# Sheet2.net
KiCad netlist of a schematic drawn in Altium Designer
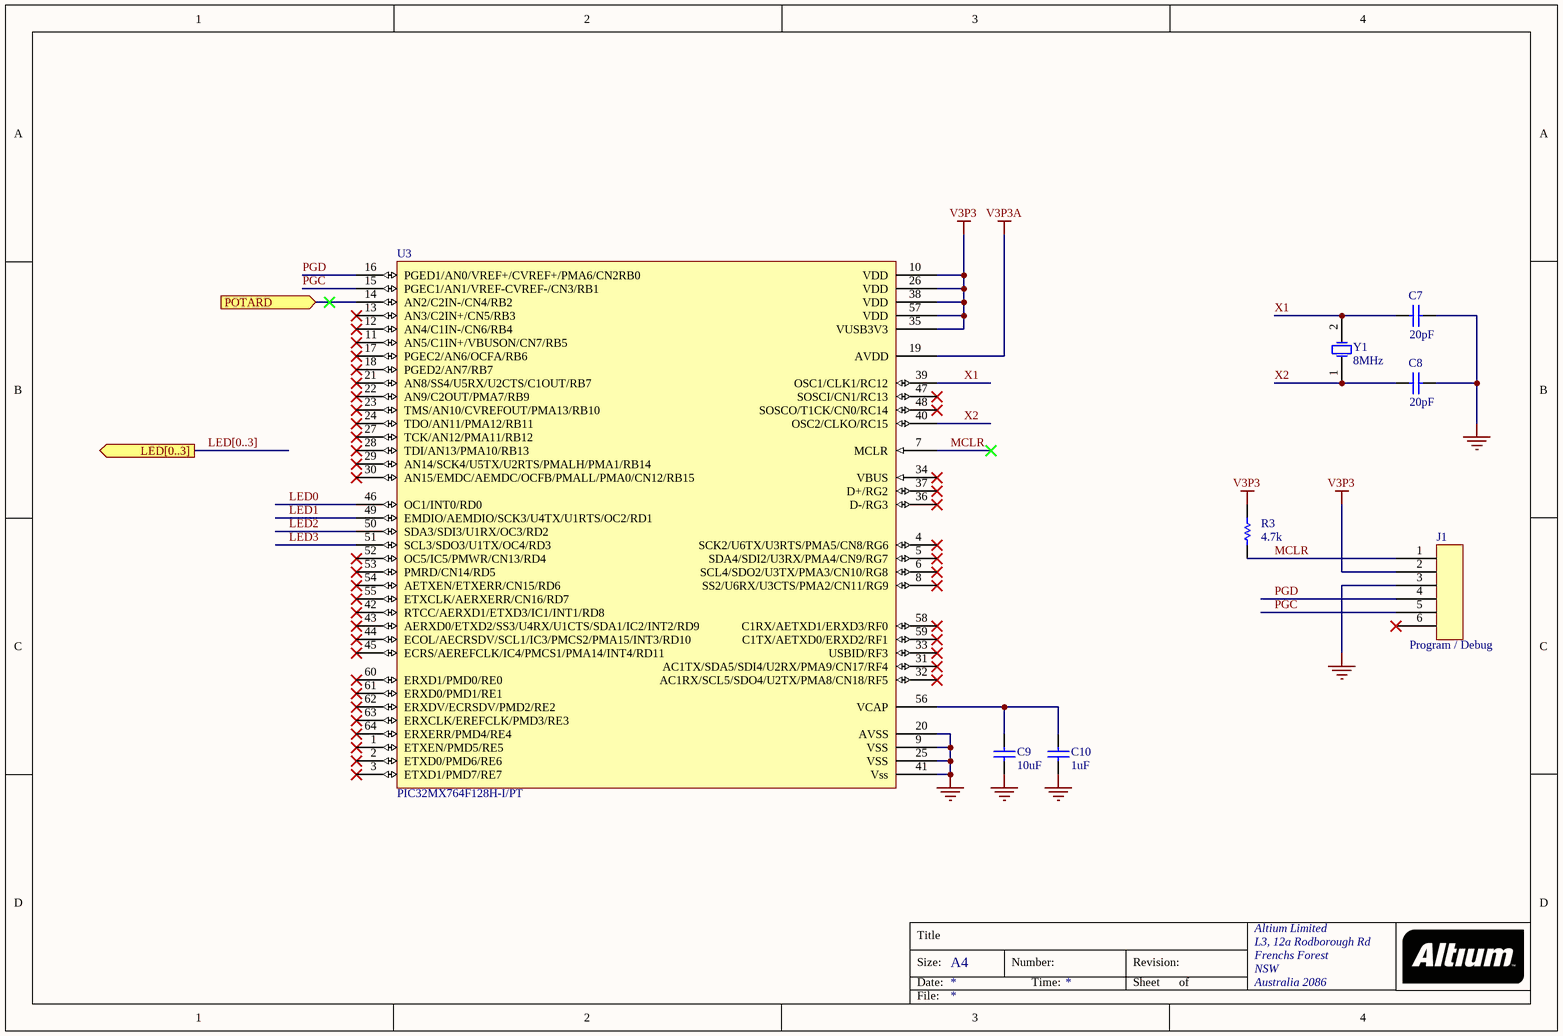
[diagram p0: Sheet2.SchDoc]

(export (version "E")
  (design (tool "Eeschema 10.0.6"))
  (components
    (comp (ref "C7")
      (value "20pF")
      (footprint "RAD-0.3")
      (description "Capacitor")
      (fields (field (name "Comment") "Cap") (field (name "PUBLISHER") "Altium Limited"))
      (libsource (lib "Miscellaneous Devices") (part "Cap"))
    )
    (comp (ref "C8")
      (value "20pF")
      (footprint "RAD-0.3")
      (description "Capacitor")
      (fields (field (name "Comment") "Cap") (field (name "PUBLISHER") "Altium Limited"))
      (libsource (lib "Miscellaneous Devices") (part "Cap"))
    )
    (comp (ref "C9")
      (value "10uF")
      (footprint "RAD-0.3")
      (description "Capacitor")
      (fields (field (name "Comment") "Cap") (field (name "PUBLISHER") "Altium Limited"))
      (libsource (lib "Miscellaneous Devices") (part "Cap"))
    )
    (comp (ref "C10")
      (value "1uF")
      (footprint "RAD-0.3")
      (description "Capacitor")
      (fields (field (name "Comment") "Cap") (field (name "PUBLISHER") "Altium Limited"))
      (libsource (lib "Miscellaneous Devices") (part "Cap"))
    )
    (comp (ref "J1") (value "Program / Debug") (libsource (lib "SchDebug") (part "Component_1")))
    (comp (ref "R3")
      (value "4.7k")
      (footprint "AXIAL-0.3")
      (description "Resistor")
      (fields (field (name "Comment") "Res1") (field (name "PUBLISHER") "Altium Limited"))
      (libsource (lib "Miscellaneous Devices") (part "Res1"))
    )
    (comp (ref "U3") (value "PIC32MX764F128H-I/PT") (libsource (lib "SchDebug") (part "PIC 32")))
    (comp (ref "Y1")
      (value "8MHz")
      (footprint "Fox Quartz")
      (description "Crystal Oscillator")
      (fields (field (name "PUBLISHER") "Altium Limited"))
      (libsource (lib "Miscellaneous Devices") (part "XTAL"))
    )
  )
  (nets
    (net (code "1") (name "/LED0") (class "Default")
      (node (ref "U3") (pin "46") (pinfunction "OC1/INT0/RD0_46") (pintype "bidirectional"))
    )
    (net (code "2") (name "/LED1") (class "Default")
      (node (ref "U3") (pin "49") (pinfunction "EMDIO/AEMDIO/SCK3/U4TX/U1RTS/OC2/RD1_49") (pintype "bidirectional"))
    )
    (net (code "3") (name "/LED2") (class "Default")
      (node (ref "U3") (pin "50") (pinfunction "SDA3/SDI3/U1RX/OC3/RD2_50") (pintype "bidirectional"))
    )
    (net (code "4") (name "/LED3") (class "Default")
      (node (ref "U3") (pin "51") (pinfunction "SCL3/SDO3/U1TX/OC4/RD3_51") (pintype "bidirectional"))
    )
    (net (code "6") (name "/MCLR") (class "Default")
      (node (ref "J1") (pin "1") (pinfunction "1_1") (pintype "passive"))
      (node (ref "R3") (pin "1") (pinfunction "1_1") (pintype "passive"))
      (node (ref "U3") (pin "7") (pinfunction "MCLR_7") (pintype "input"))
    )
    (net (code "7") (name "/PGC") (class "Default")
      (node (ref "J1") (pin "5") (pinfunction "5_5") (pintype "passive"))
      (node (ref "U3") (pin "15") (pinfunction "PGEC1/AN1/VREF-CVREF-/CN3/RB1_15") (pintype "bidirectional"))
    )
    (net (code "8") (name "/PGD") (class "Default")
      (node (ref "J1") (pin "4") (pinfunction "4_4") (pintype "passive"))
      (node (ref "U3") (pin "16") (pinfunction "PGED1/AN0/VREF+/CVREF+/PMA6/CN2RB0_16") (pintype "bidirectional"))
    )
    (net (code "9") (name "/POTARD") (class "Default")
      (node (ref "U3") (pin "14") (pinfunction "AN2/C2IN-/CN4/RB2_14") (pintype "bidirectional"))
    )
    (net (code "10") (name "/X1") (class "Default")
      (node (ref "C7") (pin "1") (pinfunction "1_1") (pintype "passive"))
      (node (ref "U3") (pin "39") (pinfunction "OSC1/CLK1/RC12_39") (pintype "bidirectional"))
      (node (ref "Y1") (pin "2") (pinfunction "OSC2_2") (pintype "passive"))
    )
    (net (code "11") (name "/X2") (class "Default")
      (node (ref "C8") (pin "1") (pinfunction "1_1") (pintype "passive"))
      (node (ref "U3") (pin "40") (pinfunction "OSC2/CLKO/RC15_40") (pintype "bidirectional"))
      (node (ref "Y1") (pin "1") (pinfunction "OSC1_1") (pintype "passive"))
    )
    (net (code "12") (name "GND") (class "Default")
      (node (ref "C10") (pin "2") (pinfunction "2_2") (pintype "passive"))
      (node (ref "C7") (pin "2") (pinfunction "2_2") (pintype "passive"))
      (node (ref "C8") (pin "2") (pinfunction "2_2") (pintype "passive"))
      (node (ref "C9") (pin "2") (pinfunction "2_2") (pintype "passive"))
      (node (ref "J1") (pin "3") (pinfunction "3_3") (pintype "passive"))
      (node (ref "U3") (pin "20") (pinfunction "AVSS_20") (pintype "passive"))
      (node (ref "U3") (pin "25") (pinfunction "VSS_25") (pintype "passive"))
      (node (ref "U3") (pin "41") (pinfunction "Vss_41") (pintype "passive"))
      (node (ref "U3") (pin "9") (pinfunction "VSS_9") (pintype "passive"))
    )
    (net (code "13") (name "Net-(U3-VCAP)") (class "Default")
      (node (ref "C10") (pin "1") (pinfunction "1_1") (pintype "passive"))
      (node (ref "C9") (pin "1") (pinfunction "1_1") (pintype "passive"))
      (node (ref "U3") (pin "56") (pinfunction "VCAP_56") (pintype "passive"))
    )
    (net (code "14") (name "V3P3") (class "Default")
      (node (ref "J1") (pin "2") (pinfunction "2_2") (pintype "passive"))
      (node (ref "R3") (pin "2") (pinfunction "2_2") (pintype "passive"))
      (node (ref "U3") (pin "10") (pinfunction "VDD_10") (pintype "passive"))
      (node (ref "U3") (pin "26") (pinfunction "VDD_26") (pintype "passive"))
      (node (ref "U3") (pin "35") (pinfunction "VUSB3V3_35") (pintype "passive"))
      (node (ref "U3") (pin "38") (pinfunction "VDD_38") (pintype "passive"))
      (node (ref "U3") (pin "57") (pinfunction "VDD_57") (pintype "passive"))
    )
    (net (code "15") (name "V3P3A") (class "Default")
      (node (ref "U3") (pin "19") (pinfunction "AVDD_19") (pintype "passive"))
    )
    (net (code "16") (name "unconnected-(J1-Pad6)") (class "Default")
      (node (ref "J1") (pin "6") (pinfunction "6_6") (pintype "passive+no_connect"))
    )
    (net (code "17") (name "unconnected-(U3-AC1RX{slash}SCL5{slash}SDO4{slash}U2TX{slash}PMA8{slash}CN18{slash}RF5-Pad32)") (class "Default")
      (node (ref "U3") (pin "32") (pinfunction "AC1RX/SCL5/SDO4/U2TX/PMA8/CN18/RF5_32") (pintype "bidirectional+no_connect"))
    )
    (net (code "18") (name "unconnected-(U3-AC1TX{slash}SDA5{slash}SDI4{slash}U2RX{slash}PMA9{slash}CN17{slash}RF4-Pad31)") (class "Default")
      (node (ref "U3") (pin "31") (pinfunction "AC1TX/SDA5/SDI4/U2RX/PMA9/CN17/RF4_31") (pintype "bidirectional+no_connect"))
    )
    (net (code "19") (name "unconnected-(U3-AERXD0{slash}ETXD2{slash}SS3{slash}U4RX{slash}U1CTS{slash}SDA1{slash}IC2{slash}INT2{slash}RD9-Pad43)") (class "Default")
      (node (ref "U3") (pin "43") (pinfunction "AERXD0/ETXD2/SS3/U4RX/U1CTS/SDA1/IC2/INT2/RD9_43") (pintype "bidirectional+no_connect"))
    )
    (net (code "20") (name "unconnected-(U3-AETXEN{slash}ETXERR{slash}CN15{slash}RD6-Pad54)") (class "Default")
      (node (ref "U3") (pin "54") (pinfunction "AETXEN/ETXERR/CN15/RD6_54") (pintype "bidirectional+no_connect"))
    )
    (net (code "21") (name "unconnected-(U3-AN3{slash}C2IN+{slash}CN5{slash}RB3-Pad13)") (class "Default")
      (node (ref "U3") (pin "13") (pinfunction "AN3/C2IN+/CN5/RB3_13") (pintype "bidirectional+no_connect"))
    )
    (net (code "22") (name "unconnected-(U3-AN4{slash}C1IN-{slash}CN6{slash}RB4-Pad12)") (class "Default")
      (node (ref "U3") (pin "12") (pinfunction "AN4/C1IN-/CN6/RB4_12") (pintype "bidirectional+no_connect"))
    )
    (net (code "23") (name "unconnected-(U3-AN5{slash}C1IN+{slash}VBUSON{slash}CN7{slash}RB5-Pad11)") (class "Default")
      (node (ref "U3") (pin "11") (pinfunction "AN5/C1IN+/VBUSON/CN7/RB5_11") (pintype "bidirectional+no_connect"))
    )
    (net (code "24") (name "unconnected-(U3-AN8{slash}SS4{slash}U5RX{slash}U2CTS{slash}C1OUT{slash}RB7-Pad21)") (class "Default")
      (node (ref "U3") (pin "21") (pinfunction "AN8/SS4/U5RX/U2CTS/C1OUT/RB7_21") (pintype "bidirectional+no_connect"))
    )
    (net (code "25") (name "unconnected-(U3-AN9{slash}C2OUT{slash}PMA7{slash}RB9-Pad22)") (class "Default")
      (node (ref "U3") (pin "22") (pinfunction "AN9/C2OUT/PMA7/RB9_22") (pintype "bidirectional+no_connect"))
    )
    (net (code "26") (name "unconnected-(U3-AN14{slash}SCK4{slash}U5TX{slash}U2RTS{slash}PMALH{slash}PMA1{slash}RB14-Pad29)") (class "Default")
      (node (ref "U3") (pin "29") (pinfunction "AN14/SCK4/U5TX/U2RTS/PMALH/PMA1/RB14_29") (pintype "bidirectional+no_connect"))
    )
    (net (code "27") (name "unconnected-(U3-AN15{slash}EMDC{slash}AEMDC{slash}OCFB{slash}PMALL{slash}PMA0{slash}CN12{slash}RB15-Pad30)") (class "Default")
      (node (ref "U3") (pin "30") (pinfunction "AN15/EMDC/AEMDC/OCFB/PMALL/PMA0/CN12/RB15_30") (pintype "bidirectional+no_connect"))
    )
    (net (code "28") (name "unconnected-(U3-C1RX{slash}AETXD1{slash}ERXD3{slash}RF0-Pad58)") (class "Default")
      (node (ref "U3") (pin "58") (pinfunction "C1RX/AETXD1/ERXD3/RF0_58") (pintype "bidirectional+no_connect"))
    )
    (net (code "29") (name "unconnected-(U3-C1TX{slash}AETXD0{slash}ERXD2{slash}RF1-Pad59)") (class "Default")
      (node (ref "U3") (pin "59") (pinfunction "C1TX/AETXD0/ERXD2/RF1_59") (pintype "bidirectional+no_connect"))
    )
    (net (code "30") (name "unconnected-(U3-D+{slash}RG2-Pad37)") (class "Default")
      (node (ref "U3") (pin "37") (pinfunction "D+/RG2_37") (pintype "bidirectional+no_connect"))
    )
    (net (code "31") (name "unconnected-(U3-D-{slash}RG3-Pad36)") (class "Default")
      (node (ref "U3") (pin "36") (pinfunction "D-/RG3_36") (pintype "bidirectional+no_connect"))
    )
    (net (code "32") (name "unconnected-(U3-ECOL{slash}AECRSDV{slash}SCL1{slash}IC3{slash}PMCS2{slash}PMA15{slash}INT3{slash}RD10-Pad44)") (class "Default")
      (node (ref "U3") (pin "44") (pinfunction "ECOL/AECRSDV/SCL1/IC3/PMCS2/PMA15/INT3/RD10_44") (pintype "bidirectional+no_connect"))
    )
    (net (code "33") (name "unconnected-(U3-ECRS{slash}AEREFCLK{slash}IC4{slash}PMCS1{slash}PMA14{slash}INT4{slash}RD11-Pad45)") (class "Default")
      (node (ref "U3") (pin "45") (pinfunction "ECRS/AEREFCLK/IC4/PMCS1/PMA14/INT4/RD11_45") (pintype "bidirectional+no_connect"))
    )
    (net (code "34") (name "unconnected-(U3-ERXCLK{slash}EREFCLK{slash}PMD3{slash}RE3-Pad63)") (class "Default")
      (node (ref "U3") (pin "63") (pinfunction "ERXCLK/EREFCLK/PMD3/RE3_63") (pintype "bidirectional+no_connect"))
    )
    (net (code "35") (name "unconnected-(U3-ERXD0{slash}PMD1{slash}RE1-Pad61)") (class "Default")
      (node (ref "U3") (pin "61") (pinfunction "ERXD0/PMD1/RE1_61") (pintype "bidirectional+no_connect"))
    )
    (net (code "36") (name "unconnected-(U3-ERXD1{slash}PMD0{slash}RE0-Pad60)") (class "Default")
      (node (ref "U3") (pin "60") (pinfunction "ERXD1/PMD0/RE0_60") (pintype "bidirectional+no_connect"))
    )
    (net (code "37") (name "unconnected-(U3-ERXDV{slash}ECRSDV{slash}PMD2{slash}RE2-Pad62)") (class "Default")
      (node (ref "U3") (pin "62") (pinfunction "ERXDV/ECRSDV/PMD2/RE2_62") (pintype "bidirectional+no_connect"))
    )
    (net (code "38") (name "unconnected-(U3-ERXERR{slash}PMD4{slash}RE4-Pad64)") (class "Default")
      (node (ref "U3") (pin "64") (pinfunction "ERXERR/PMD4/RE4_64") (pintype "bidirectional+no_connect"))
    )
    (net (code "39") (name "unconnected-(U3-ETXCLK{slash}AERXERR{slash}CN16{slash}RD7-Pad55)") (class "Default")
      (node (ref "U3") (pin "55") (pinfunction "ETXCLK/AERXERR/CN16/RD7_55") (pintype "bidirectional+no_connect"))
    )
    (net (code "40") (name "unconnected-(U3-ETXD0{slash}PMD6{slash}RE6-Pad2)") (class "Default")
      (node (ref "U3") (pin "2") (pinfunction "ETXD0/PMD6/RE6_2") (pintype "bidirectional+no_connect"))
    )
    (net (code "41") (name "unconnected-(U3-ETXD1{slash}PMD7{slash}RE7-Pad3)") (class "Default")
      (node (ref "U3") (pin "3") (pinfunction "ETXD1/PMD7/RE7_3") (pintype "bidirectional+no_connect"))
    )
    (net (code "42") (name "unconnected-(U3-ETXEN{slash}PMD5{slash}RE5-Pad1)") (class "Default")
      (node (ref "U3") (pin "1") (pinfunction "ETXEN/PMD5/RE5_1") (pintype "bidirectional+no_connect"))
    )
    (net (code "43") (name "unconnected-(U3-OC5{slash}IC5{slash}PMWR{slash}CN13{slash}RD4-Pad52)") (class "Default")
      (node (ref "U3") (pin "52") (pinfunction "OC5/IC5/PMWR/CN13/RD4_52") (pintype "bidirectional+no_connect"))
    )
    (net (code "44") (name "unconnected-(U3-PGEC2{slash}AN6{slash}OCFA{slash}RB6-Pad17)") (class "Default")
      (node (ref "U3") (pin "17") (pinfunction "PGEC2/AN6/OCFA/RB6_17") (pintype "bidirectional+no_connect"))
    )
    (net (code "45") (name "unconnected-(U3-PGED2{slash}AN7{slash}RB7-Pad18)") (class "Default")
      (node (ref "U3") (pin "18") (pinfunction "PGED2/AN7/RB7_18") (pintype "bidirectional+no_connect"))
    )
    (net (code "46") (name "unconnected-(U3-PMRD{slash}CN14{slash}RD5-Pad53)") (class "Default")
      (node (ref "U3") (pin "53") (pinfunction "PMRD/CN14/RD5_53") (pintype "bidirectional+no_connect"))
    )
    (net (code "47") (name "unconnected-(U3-RTCC{slash}AERXD1{slash}ETXD3{slash}IC1{slash}INT1{slash}RD8-Pad42)") (class "Default")
      (node (ref "U3") (pin "42") (pinfunction "RTCC/AERXD1/ETXD3/IC1/INT1/RD8_42") (pintype "bidirectional+no_connect"))
    )
    (net (code "48") (name "unconnected-(U3-SCK2{slash}U6TX{slash}U3RTS{slash}PMA5{slash}CN8{slash}RG6-Pad4)") (class "Default")
      (node (ref "U3") (pin "4") (pinfunction "SCK2/U6TX/U3RTS/PMA5/CN8/RG6_4") (pintype "bidirectional+no_connect"))
    )
    (net (code "49") (name "unconnected-(U3-SCL4{slash}SDO2{slash}U3TX{slash}PMA3{slash}CN10{slash}RG8-Pad6)") (class "Default")
      (node (ref "U3") (pin "6") (pinfunction "SCL4/SDO2/U3TX/PMA3/CN10/RG8_6") (pintype "bidirectional+no_connect"))
    )
    (net (code "50") (name "unconnected-(U3-SDA4{slash}SDI2{slash}U3RX{slash}PMA4{slash}CN9{slash}RG7-Pad5)") (class "Default")
      (node (ref "U3") (pin "5") (pinfunction "SDA4/SDI2/U3RX/PMA4/CN9/RG7_5") (pintype "bidirectional+no_connect"))
    )
    (net (code "51") (name "unconnected-(U3-SOSCI{slash}CN1{slash}RC13-Pad47)") (class "Default")
      (node (ref "U3") (pin "47") (pinfunction "SOSCI/CN1/RC13_47") (pintype "bidirectional+no_connect"))
    )
    (net (code "52") (name "unconnected-(U3-SOSCO{slash}T1CK{slash}CN0{slash}RC14-Pad48)") (class "Default")
      (node (ref "U3") (pin "48") (pinfunction "SOSCO/T1CK/CN0/RC14_48") (pintype "bidirectional+no_connect"))
    )
    (net (code "53") (name "unconnected-(U3-SS2{slash}U6RX{slash}U3CTS{slash}PMA2{slash}CN11{slash}RG9-Pad8)") (class "Default")
      (node (ref "U3") (pin "8") (pinfunction "SS2/U6RX/U3CTS/PMA2/CN11/RG9_8") (pintype "bidirectional+no_connect"))
    )
    (net (code "54") (name "unconnected-(U3-TCK{slash}AN12{slash}PMA11{slash}RB12-Pad27)") (class "Default")
      (node (ref "U3") (pin "27") (pinfunction "TCK/AN12/PMA11/RB12_27") (pintype "bidirectional+no_connect"))
    )
    (net (code "55") (name "unconnected-(U3-TDI{slash}AN13{slash}PMA10{slash}RB13-Pad28)") (class "Default")
      (node (ref "U3") (pin "28") (pinfunction "TDI/AN13/PMA10/RB13_28") (pintype "bidirectional+no_connect"))
    )
    (net (code "56") (name "unconnected-(U3-TDO{slash}AN11{slash}PMA12{slash}RB11-Pad24)") (class "Default")
      (node (ref "U3") (pin "24") (pinfunction "TDO/AN11/PMA12/RB11_24") (pintype "bidirectional+no_connect"))
    )
    (net (code "57") (name "unconnected-(U3-TMS{slash}AN10{slash}CVREFOUT{slash}PMA13{slash}RB10-Pad23)") (class "Default")
      (node (ref "U3") (pin "23") (pinfunction "TMS/AN10/CVREFOUT/PMA13/RB10_23") (pintype "bidirectional+no_connect"))
    )
    (net (code "58") (name "unconnected-(U3-USBID{slash}RF3-Pad33)") (class "Default")
      (node (ref "U3") (pin "33") (pinfunction "USBID/RF3_33") (pintype "bidirectional+no_connect"))
    )
    (net (code "59") (name "unconnected-(U3-VBUS-Pad34)") (class "Default")
      (node (ref "U3") (pin "34") (pinfunction "VBUS_34") (pintype "input+no_connect"))
    )
  )
)
